# A_INPUT.net
KiCad netlist of a schematic drawn in Altium Designer
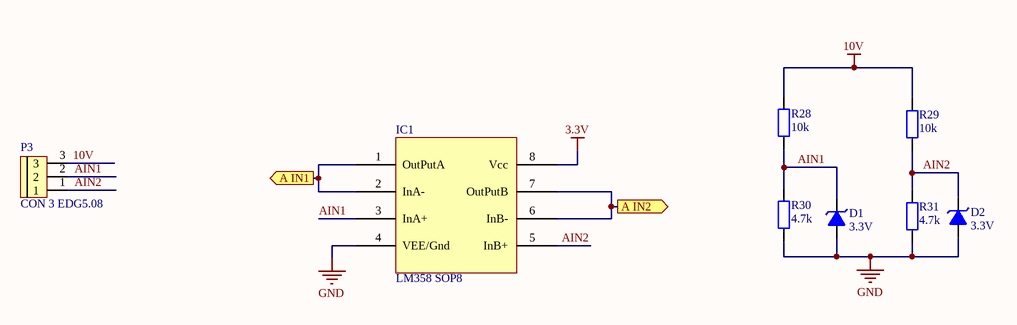
[diagram p0: A_INPUT.SchDoc]

(export (version "E")
  (design (tool "Eeschema 10.0.6"))
  (components
    (comp (ref "D1")
      (value "3.3V")
      (footprint "DIODE ZENNER SMD SOD80")
      (description "Dán")
      (libsource (lib "Altium_Lib_by_KhueNguyenCreator") (part "Diode Zener 3.3V"))
    )
    (comp (ref "D2")
      (value "3.3V")
      (footprint "DIODE ZENNER SMD SOD80")
      (description "Dán")
      (libsource (lib "Altium_Lib_by_KhueNguyenCreator") (part "Diode Zener 3.3V"))
    )
    (comp (ref "IC1")
      (value "LM358 SOP8")
      (footprint "SOP 8")
      (description "Dán")
      (libsource (lib "Altium_Lib_by_KhueNguyenCreator") (part "LM358 SOP8"))
    )
    (comp (ref "P3")
      (value "CON 3 EDG5.08")
      (footprint "CON 3 3EDG5.08")
      (description "Cắm")
      (libsource (lib "Altium_Lib_by_KhueNguyenCreator") (part "CON 3 EDG5.08"))
    )
    (comp (ref "R28")
      (value "10k")
      (footprint "tro smd 0805")
      (description "Dán")
      (libsource (lib "Altium_Lib_by_KhueNguyenCreator") (part "Tro 0805 5% 10k"))
    )
    (comp (ref "R29")
      (value "10k")
      (footprint "tro smd 0805")
      (description "Dán")
      (libsource (lib "Altium_Lib_by_KhueNguyenCreator") (part "Tro 0805 5% 10k"))
    )
    (comp (ref "R30")
      (value "4.7k")
      (footprint "tro smd 0805")
      (description "Dán")
      (libsource (lib "Altium_Lib_by_KhueNguyenCreator") (part "Tro 0805 5% 4.7k"))
    )
    (comp (ref "R31")
      (value "4.7k")
      (footprint "tro smd 0805")
      (description "Dán")
      (libsource (lib "Altium_Lib_by_KhueNguyenCreator") (part "Tro 0805 5% 4.7k"))
    )
  )
  (nets
    (net (code "1") (name "/A IN1") (class "Default")
      (node (ref "IC1") (pin "1") (pinfunction "OutPutA_1") (pintype "passive"))
      (node (ref "IC1") (pin "2") (pinfunction "InA-_2") (pintype "passive"))
    )
    (net (code "2") (name "/A IN2") (class "Default")
      (node (ref "IC1") (pin "6") (pinfunction "InB-_6") (pintype "passive"))
      (node (ref "IC1") (pin "7") (pinfunction "OutPutB_7") (pintype "passive"))
    )
    (net (code "3") (name "/AIN1") (class "Default")
      (node (ref "D1") (pin "2") (pinfunction "K_2") (pintype "passive"))
      (node (ref "IC1") (pin "3") (pinfunction "InA+_3") (pintype "passive"))
      (node (ref "P3") (pin "2") (pinfunction "2_2") (pintype "passive"))
      (node (ref "R28") (pin "1") (pinfunction "1_1") (pintype "passive"))
      (node (ref "R30") (pin "2") (pinfunction "2_2") (pintype "passive"))
    )
    (net (code "4") (name "/AIN2") (class "Default")
      (node (ref "D2") (pin "2") (pinfunction "K_2") (pintype "passive"))
      (node (ref "IC1") (pin "5") (pinfunction "InB+_5") (pintype "passive"))
      (node (ref "P3") (pin "1") (pinfunction "1_1") (pintype "passive"))
      (node (ref "R29") (pin "1") (pinfunction "1_1") (pintype "passive"))
      (node (ref "R31") (pin "2") (pinfunction "2_2") (pintype "passive"))
    )
    (net (code "5") (name "3.3V") (class "Default")
      (node (ref "IC1") (pin "8") (pinfunction "Vcc_8") (pintype "passive"))
    )
    (net (code "6") (name "10V") (class "Default")
      (node (ref "P3") (pin "3") (pinfunction "3_3") (pintype "passive"))
      (node (ref "R28") (pin "2") (pinfunction "2_2") (pintype "passive"))
      (node (ref "R29") (pin "2") (pinfunction "2_2") (pintype "passive"))
    )
    (net (code "7") (name "GND") (class "Default")
      (node (ref "D1") (pin "1") (pinfunction "A_1") (pintype "passive"))
      (node (ref "D2") (pin "1") (pinfunction "A_1") (pintype "passive"))
      (node (ref "IC1") (pin "4") (pinfunction "VEE/Gnd_4") (pintype "passive"))
      (node (ref "R30") (pin "1") (pinfunction "1_1") (pintype "passive"))
      (node (ref "R31") (pin "1") (pinfunction "1_1") (pintype "passive"))
    )
  )
)
